# Planar_HB_2.net
KiCad netlist of a schematic drawn in Altium Designer
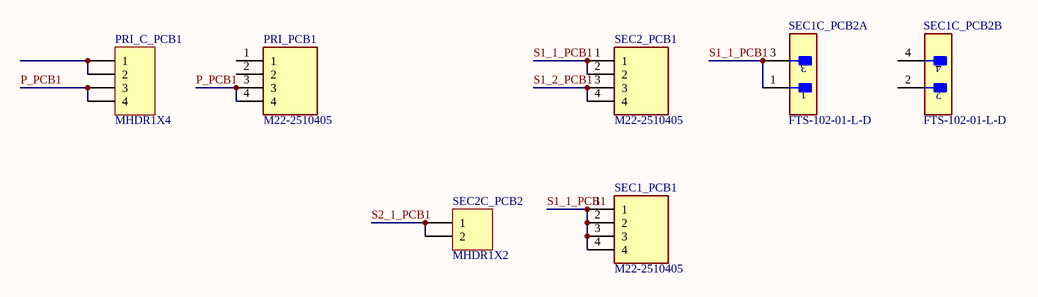
[diagram p0: Planar_HB_2.SchDoc]

(export (version "E")
  (design (tool "Eeschema 10.0.6"))
  (components
    (comp (ref "PRI_C_PCB1")
      (value "MHDR1X4")
      (footprint "MHDR1X4")
      (description "Header, 4-Pin")
      (fields (field (name "PUBLISHER") "Altium Limited"))
      (libsource (lib "Miscellaneous Connectors") (part "MHDR1X4"))
    )
    (comp (ref "PRI_PCB1")
      (value "M22-2510405")
      (footprint "SamacSys:HDRV4W50P0X200_1X4_800X200X525P")
      (description "Connector")
      (fields (field (name "MOUSER PART NUMBER") "855-M22-2510405"))
      (libsource (lib "*") (part "M22-2510405"))
    )
    (comp (ref "SEC1C_PCB2")
      (value "FTS-102-01-L-D")
      (footprint "FP-FTS-102-01-L-D-MFG")
      (description "CONN HEADER VERT 4POS 1.27MM")
      (libsource (lib "Altium Content Vault") (part "1621473add15499e993d6bbd36d0f06"))
    )
    (comp (ref "SEC1_PCB1")
      (value "M22-2510405")
      (footprint "SamacSys:HDRV4W50P0X200_1X4_800X200X525P")
      (description "Connector")
      (fields (field (name "MOUSER PART NUMBER") "855-M22-2510405"))
      (libsource (lib "*") (part "M22-2510405"))
    )
    (comp (ref "SEC2C_PCB2")
      (value "MHDR1X2")
      (footprint "MHDR1X2")
      (description "Header, 2-Pin")
      (fields (field (name "PUBLISHER") "Altium Limited"))
      (libsource (lib "Miscellaneous Connectors") (part "MHDR1X2"))
    )
    (comp (ref "SEC2_PCB1")
      (value "M22-2510405")
      (footprint "SamacSys:HDRV4W50P0X200_1X4_800X200X525P")
      (description "Connector")
      (fields (field (name "MOUSER PART NUMBER") "855-M22-2510405"))
      (libsource (lib "*") (part "M22-2510405"))
    )
  )
  (nets
    (net (code "1") (name "/P_PCB1") (class "Default")
      (node (ref "PRI_C_PCB1") (pin "3") (pinfunction "3_3") (pintype "passive"))
      (node (ref "PRI_C_PCB1") (pin "4") (pinfunction "4_4") (pintype "passive"))
      (node (ref "PRI_PCB1") (pin "3") (pinfunction "3_3") (pintype "passive"))
      (node (ref "PRI_PCB1") (pin "4") (pinfunction "4_4") (pintype "passive"))
    )
    (net (code "2") (name "/S1_1_PCB1") (class "Default")
      (node (ref "SEC1C_PCB2") (pin "1") (pinfunction "1_1") (pintype "passive"))
      (node (ref "SEC1C_PCB2") (pin "3") (pinfunction "3_3") (pintype "passive"))
      (node (ref "SEC1_PCB1") (pin "1") (pinfunction "1_1") (pintype "passive"))
      (node (ref "SEC1_PCB1") (pin "2") (pinfunction "2_2") (pintype "passive"))
      (node (ref "SEC1_PCB1") (pin "3") (pinfunction "3_3") (pintype "passive"))
      (node (ref "SEC1_PCB1") (pin "4") (pinfunction "4_4") (pintype "passive"))
      (node (ref "SEC2_PCB1") (pin "1") (pinfunction "1_1") (pintype "passive"))
      (node (ref "SEC2_PCB1") (pin "2") (pinfunction "2_2") (pintype "passive"))
    )
    (net (code "3") (name "/S1_2_PCB1") (class "Default")
      (node (ref "SEC2_PCB1") (pin "3") (pinfunction "3_3") (pintype "passive"))
      (node (ref "SEC2_PCB1") (pin "4") (pinfunction "4_4") (pintype "passive"))
    )
    (net (code "4") (name "/S2_1_PCB1") (class "Default")
      (node (ref "SEC2C_PCB2") (pin "1") (pinfunction "1_1") (pintype "passive"))
      (node (ref "SEC2C_PCB2") (pin "2") (pinfunction "2_2") (pintype "passive"))
    )
    (net (code "5") (name "Net-(PRI_C_PCB1-Pad1)") (class "Default")
      (node (ref "PRI_C_PCB1") (pin "1") (pinfunction "1_1") (pintype "passive"))
      (node (ref "PRI_C_PCB1") (pin "2") (pinfunction "2_2") (pintype "passive"))
    )
    (net (code "6") (name "unconnected-(PRI_PCB1-Pad1)") (class "Default")
      (node (ref "PRI_PCB1") (pin "1") (pinfunction "1_1") (pintype "passive"))
    )
    (net (code "7") (name "unconnected-(PRI_PCB1-Pad2)") (class "Default")
      (node (ref "PRI_PCB1") (pin "2") (pinfunction "2_2") (pintype "passive"))
    )
    (net (code "8") (name "unconnected-(SEC1C_PCB2-Pad2)") (class "Default")
      (node (ref "SEC1C_PCB2") (pin "2") (pinfunction "2_2") (pintype "passive"))
    )
    (net (code "9") (name "unconnected-(SEC1C_PCB2-Pad4)") (class "Default")
      (node (ref "SEC1C_PCB2") (pin "4") (pinfunction "4_4") (pintype "passive"))
    )
  )
)
